# photodiodes.net
KiCad netlist of a schematic drawn in Altium Designer
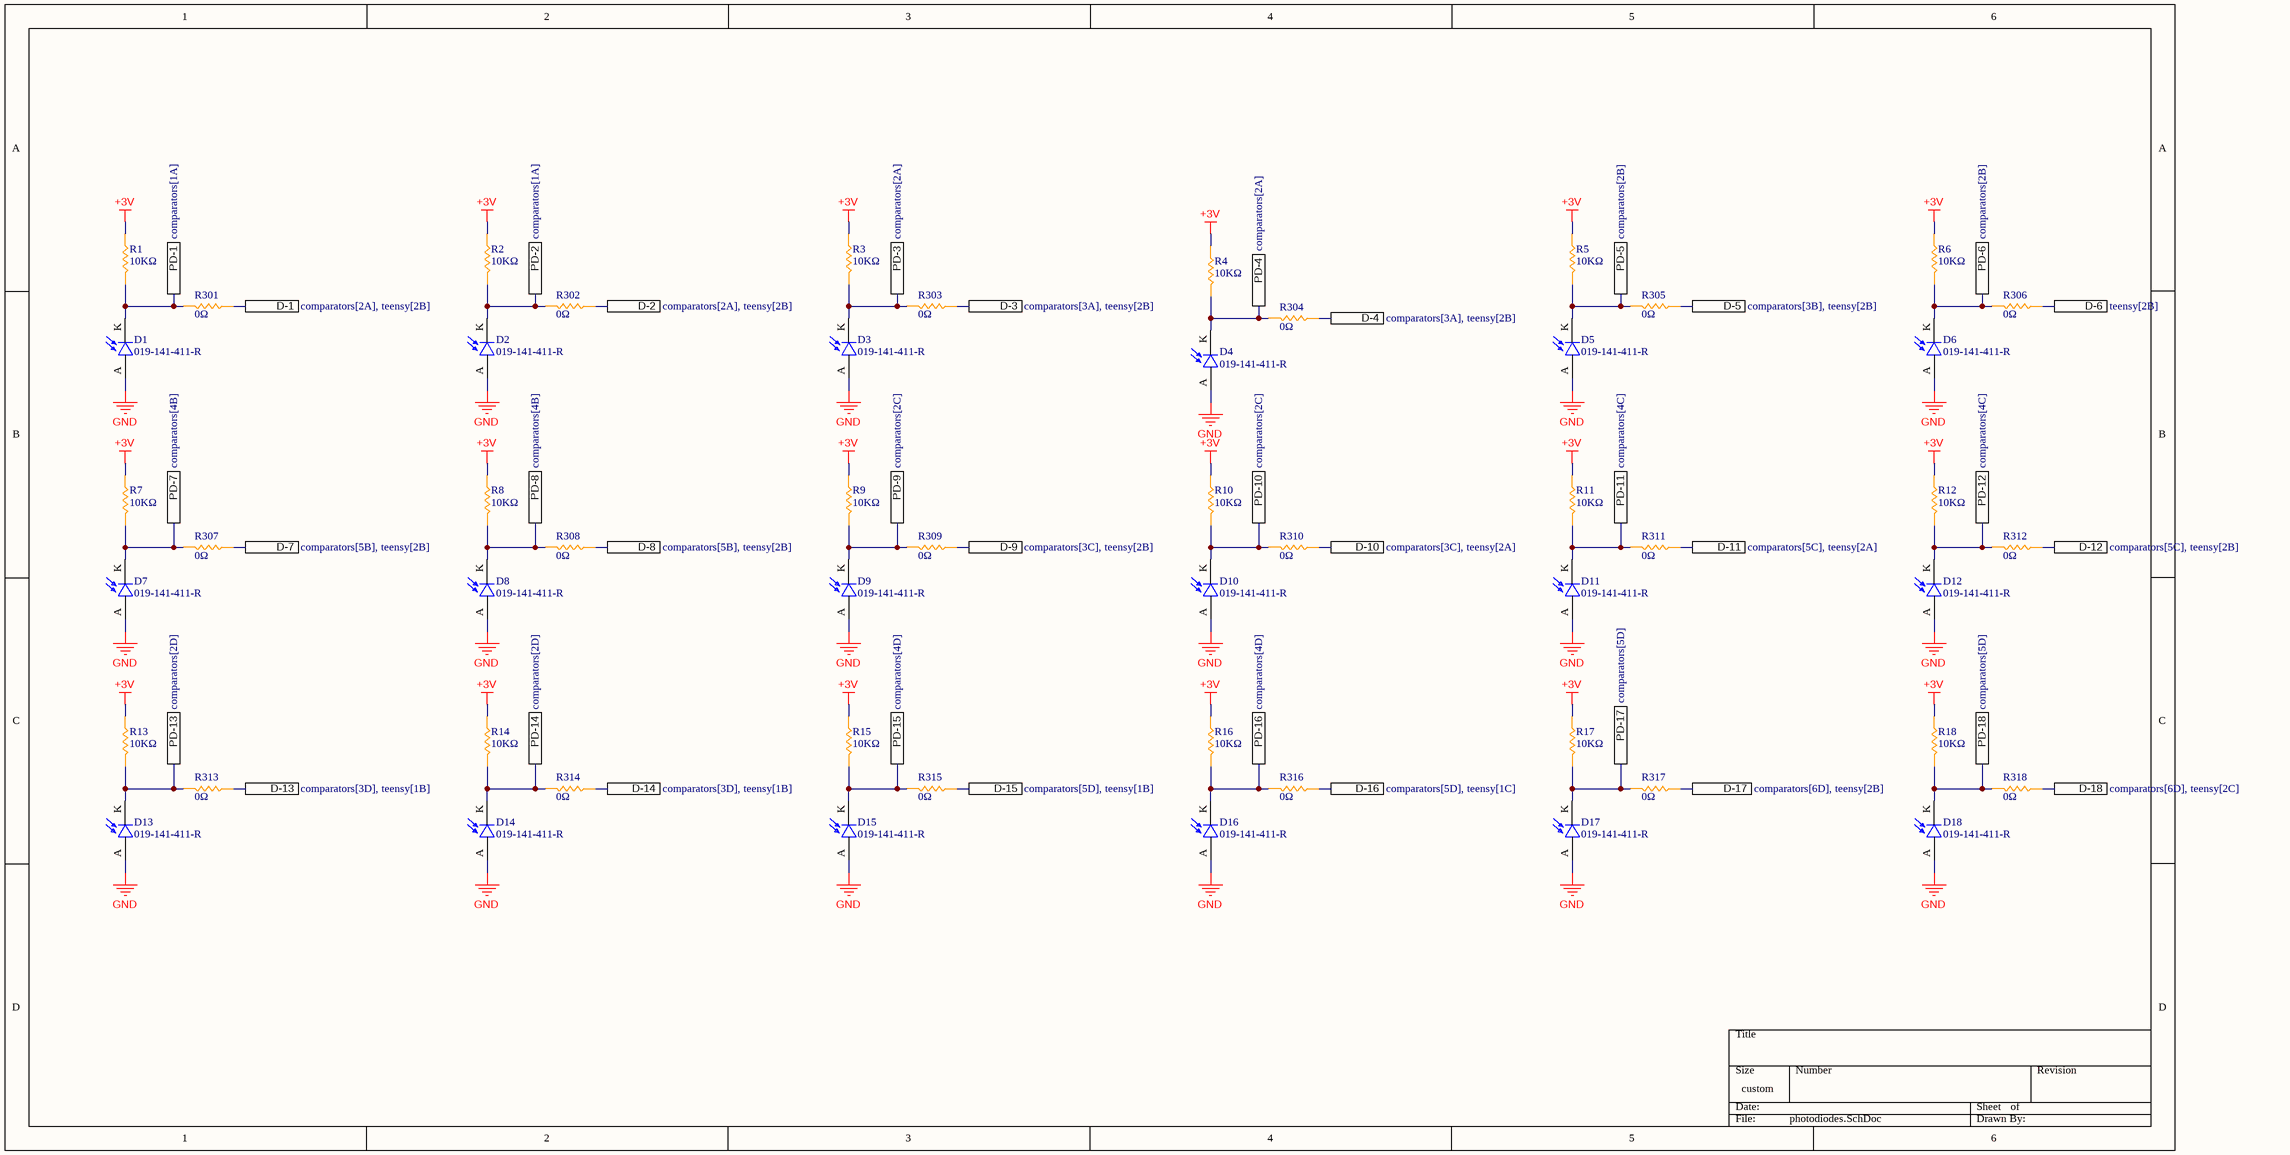
[diagram p0: photodiodes.SchDoc]

(export (version "E")
  (design (tool "Eeschema 10.0.6"))
  (components
    (comp (ref "D1")
      (value "019-141-411-R")
      (footprint "DIOC2012X80N")
      (description "PHOTODIODE RED MICRO SMT")
      (fields (field (name "MF") "Advanced Photonix"))
      (libsource (lib "019-141-411-R") (part "019-141-411-R"))
    )
    (comp (ref "D2")
      (value "019-141-411-R")
      (footprint "DIOC2012X80N")
      (description "PHOTODIODE RED MICRO SMT")
      (fields (field (name "MF") "Advanced Photonix"))
      (libsource (lib "019-141-411-R") (part "019-141-411-R"))
    )
    (comp (ref "D3")
      (value "019-141-411-R")
      (footprint "DIOC2012X80N")
      (description "PHOTODIODE RED MICRO SMT")
      (fields (field (name "MF") "Advanced Photonix"))
      (libsource (lib "019-141-411-R") (part "019-141-411-R"))
    )
    (comp (ref "D4")
      (value "019-141-411-R")
      (footprint "DIOC2012X80N")
      (description "PHOTODIODE RED MICRO SMT")
      (fields (field (name "MF") "Advanced Photonix"))
      (libsource (lib "019-141-411-R") (part "019-141-411-R"))
    )
    (comp (ref "D5")
      (value "019-141-411-R")
      (footprint "DIOC2012X80N")
      (description "PHOTODIODE RED MICRO SMT")
      (fields (field (name "MF") "Advanced Photonix"))
      (libsource (lib "019-141-411-R") (part "019-141-411-R"))
    )
    (comp (ref "D6")
      (value "019-141-411-R")
      (footprint "DIOC2012X80N")
      (description "PHOTODIODE RED MICRO SMT")
      (fields (field (name "MF") "Advanced Photonix"))
      (libsource (lib "019-141-411-R") (part "019-141-411-R"))
    )
    (comp (ref "D7")
      (value "019-141-411-R")
      (footprint "DIOC2012X80N")
      (description "PHOTODIODE RED MICRO SMT")
      (fields (field (name "MF") "Advanced Photonix"))
      (libsource (lib "019-141-411-R") (part "019-141-411-R"))
    )
    (comp (ref "D8")
      (value "019-141-411-R")
      (footprint "DIOC2012X80N")
      (description "PHOTODIODE RED MICRO SMT")
      (fields (field (name "MF") "Advanced Photonix"))
      (libsource (lib "019-141-411-R") (part "019-141-411-R"))
    )
    (comp (ref "D9")
      (value "019-141-411-R")
      (footprint "DIOC2012X80N")
      (description "PHOTODIODE RED MICRO SMT")
      (fields (field (name "MF") "Advanced Photonix"))
      (libsource (lib "019-141-411-R") (part "019-141-411-R"))
    )
    (comp (ref "D10")
      (value "019-141-411-R")
      (footprint "DIOC2012X80N")
      (description "PHOTODIODE RED MICRO SMT")
      (fields (field (name "MF") "Advanced Photonix"))
      (libsource (lib "019-141-411-R") (part "019-141-411-R"))
    )
    (comp (ref "D11")
      (value "019-141-411-R")
      (footprint "DIOC2012X80N")
      (description "PHOTODIODE RED MICRO SMT")
      (fields (field (name "MF") "Advanced Photonix"))
      (libsource (lib "019-141-411-R") (part "019-141-411-R"))
    )
    (comp (ref "D12")
      (value "019-141-411-R")
      (footprint "DIOC2012X80N")
      (description "PHOTODIODE RED MICRO SMT")
      (fields (field (name "MF") "Advanced Photonix"))
      (libsource (lib "019-141-411-R") (part "019-141-411-R"))
    )
    (comp (ref "D13")
      (value "019-141-411-R")
      (footprint "DIOC2012X80N")
      (description "PHOTODIODE RED MICRO SMT")
      (fields (field (name "MF") "Advanced Photonix"))
      (libsource (lib "019-141-411-R") (part "019-141-411-R"))
    )
    (comp (ref "D14")
      (value "019-141-411-R")
      (footprint "DIOC2012X80N")
      (description "PHOTODIODE RED MICRO SMT")
      (fields (field (name "MF") "Advanced Photonix"))
      (libsource (lib "019-141-411-R") (part "019-141-411-R"))
    )
    (comp (ref "D15")
      (value "019-141-411-R")
      (footprint "DIOC2012X80N")
      (description "PHOTODIODE RED MICRO SMT")
      (fields (field (name "MF") "Advanced Photonix"))
      (libsource (lib "019-141-411-R") (part "019-141-411-R"))
    )
    (comp (ref "D16")
      (value "019-141-411-R")
      (footprint "DIOC2012X80N")
      (description "PHOTODIODE RED MICRO SMT")
      (fields (field (name "MF") "Advanced Photonix"))
      (libsource (lib "019-141-411-R") (part "019-141-411-R"))
    )
    (comp (ref "D17")
      (value "019-141-411-R")
      (footprint "DIOC2012X80N")
      (description "PHOTODIODE RED MICRO SMT")
      (fields (field (name "MF") "Advanced Photonix"))
      (libsource (lib "019-141-411-R") (part "019-141-411-R"))
    )
    (comp (ref "D18")
      (value "019-141-411-R")
      (footprint "DIOC2012X80N")
      (description "PHOTODIODE RED MICRO SMT")
      (fields (field (name "MF") "Advanced Photonix"))
      (libsource (lib "019-141-411-R") (part "019-141-411-R"))
    )
    (comp (ref "R1")
      (value "10KΩ")
      (footprint "RES_0603")
      (description "Resistor SMD 0603 generic")
      (libsource (lib "RC") (part "RES_0603"))
    )
    (comp (ref "R2")
      (value "10KΩ")
      (footprint "RES_0603")
      (description "Resistor SMD 0603 generic")
      (libsource (lib "RC") (part "RES_0603"))
    )
    (comp (ref "R3")
      (value "10KΩ")
      (footprint "RES_0603")
      (description "Resistor SMD 0603 generic")
      (libsource (lib "RC") (part "RES_0603"))
    )
    (comp (ref "R4")
      (value "10KΩ")
      (footprint "RES_0603")
      (description "Resistor SMD 0603 generic")
      (libsource (lib "RC") (part "RES_0603"))
    )
    (comp (ref "R5")
      (value "10KΩ")
      (footprint "RES_0603")
      (description "Resistor SMD 0603 generic")
      (libsource (lib "RC") (part "RES_0603"))
    )
    (comp (ref "R6")
      (value "10KΩ")
      (footprint "RES_0603")
      (description "Resistor SMD 0603 generic")
      (libsource (lib "RC") (part "RES_0603"))
    )
    (comp (ref "R7")
      (value "10KΩ")
      (footprint "RES_0603")
      (description "Resistor SMD 0603 generic")
      (libsource (lib "RC") (part "RES_0603"))
    )
    (comp (ref "R8")
      (value "10KΩ")
      (footprint "RES_0603")
      (description "Resistor SMD 0603 generic")
      (libsource (lib "RC") (part "RES_0603"))
    )
    (comp (ref "R9")
      (value "10KΩ")
      (footprint "RES_0603")
      (description "Resistor SMD 0603 generic")
      (libsource (lib "RC") (part "RES_0603"))
    )
    (comp (ref "R10")
      (value "10KΩ")
      (footprint "RES_0603")
      (description "Resistor SMD 0603 generic")
      (libsource (lib "RC") (part "RES_0603"))
    )
    (comp (ref "R11")
      (value "10KΩ")
      (footprint "RES_0603")
      (description "Resistor SMD 0603 generic")
      (libsource (lib "RC") (part "RES_0603"))
    )
    (comp (ref "R12")
      (value "10KΩ")
      (footprint "RES_0603")
      (description "Resistor SMD 0603 generic")
      (libsource (lib "RC") (part "RES_0603"))
    )
    (comp (ref "R13")
      (value "10KΩ")
      (footprint "RES_0603")
      (description "Resistor SMD 0603 generic")
      (libsource (lib "RC") (part "RES_0603"))
    )
    (comp (ref "R14")
      (value "10KΩ")
      (footprint "RES_0603")
      (description "Resistor SMD 0603 generic")
      (libsource (lib "RC") (part "RES_0603"))
    )
    (comp (ref "R15")
      (value "10KΩ")
      (footprint "RES_0603")
      (description "Resistor SMD 0603 generic")
      (libsource (lib "RC") (part "RES_0603"))
    )
    (comp (ref "R16")
      (value "10KΩ")
      (footprint "RES_0603")
      (description "Resistor SMD 0603 generic")
      (libsource (lib "RC") (part "RES_0603"))
    )
    (comp (ref "R17")
      (value "10KΩ")
      (footprint "RES_0603")
      (description "Resistor SMD 0603 generic")
      (libsource (lib "RC") (part "RES_0603"))
    )
    (comp (ref "R18")
      (value "10KΩ")
      (footprint "RES_0603")
      (description "Resistor SMD 0603 generic")
      (libsource (lib "RC") (part "RES_0603"))
    )
    (comp (ref "R301")
      (value "0Ω")
      (footprint "RES_0603")
      (description "Resistor SMD 0603 generic")
      (libsource (lib "RC") (part "RES_0603"))
    )
    (comp (ref "R302")
      (value "0Ω")
      (footprint "RES_0603")
      (description "Resistor SMD 0603 generic")
      (libsource (lib "RC") (part "RES_0603"))
    )
    (comp (ref "R303")
      (value "0Ω")
      (footprint "RES_0603")
      (description "Resistor SMD 0603 generic")
      (libsource (lib "RC") (part "RES_0603"))
    )
    (comp (ref "R304")
      (value "0Ω")
      (footprint "RES_0603")
      (description "Resistor SMD 0603 generic")
      (libsource (lib "RC") (part "RES_0603"))
    )
    (comp (ref "R305")
      (value "0Ω")
      (footprint "RES_0603")
      (description "Resistor SMD 0603 generic")
      (libsource (lib "RC") (part "RES_0603"))
    )
    (comp (ref "R306")
      (value "0Ω")
      (footprint "RES_0603")
      (description "Resistor SMD 0603 generic")
      (libsource (lib "RC") (part "RES_0603"))
    )
    (comp (ref "R307")
      (value "0Ω")
      (footprint "RES_0603")
      (description "Resistor SMD 0603 generic")
      (libsource (lib "RC") (part "RES_0603"))
    )
    (comp (ref "R308")
      (value "0Ω")
      (footprint "RES_0603")
      (description "Resistor SMD 0603 generic")
      (libsource (lib "RC") (part "RES_0603"))
    )
    (comp (ref "R309")
      (value "0Ω")
      (footprint "RES_0603")
      (description "Resistor SMD 0603 generic")
      (libsource (lib "RC") (part "RES_0603"))
    )
    (comp (ref "R310")
      (value "0Ω")
      (footprint "RES_0603")
      (description "Resistor SMD 0603 generic")
      (libsource (lib "RC") (part "RES_0603"))
    )
    (comp (ref "R311")
      (value "0Ω")
      (footprint "RES_0603")
      (description "Resistor SMD 0603 generic")
      (libsource (lib "RC") (part "RES_0603"))
    )
    (comp (ref "R312")
      (value "0Ω")
      (footprint "RES_0603")
      (description "Resistor SMD 0603 generic")
      (libsource (lib "RC") (part "RES_0603"))
    )
    (comp (ref "R313")
      (value "0Ω")
      (footprint "RES_0603")
      (description "Resistor SMD 0603 generic")
      (libsource (lib "RC") (part "RES_0603"))
    )
    (comp (ref "R314")
      (value "0Ω")
      (footprint "RES_0603")
      (description "Resistor SMD 0603 generic")
      (libsource (lib "RC") (part "RES_0603"))
    )
    (comp (ref "R315")
      (value "0Ω")
      (footprint "RES_0603")
      (description "Resistor SMD 0603 generic")
      (libsource (lib "RC") (part "RES_0603"))
    )
    (comp (ref "R316")
      (value "0Ω")
      (footprint "RES_0603")
      (description "Resistor SMD 0603 generic")
      (libsource (lib "RC") (part "RES_0603"))
    )
    (comp (ref "R317")
      (value "0Ω")
      (footprint "RES_0603")
      (description "Resistor SMD 0603 generic")
      (libsource (lib "RC") (part "RES_0603"))
    )
    (comp (ref "R318")
      (value "0Ω")
      (footprint "RES_0603")
      (description "Resistor SMD 0603 generic")
      (libsource (lib "RC") (part "RES_0603"))
    )
  )
  (nets
    (net (code "1") (name "+3V") (class "Default")
      (node (ref "R1") (pin "2") (pintype "passive"))
      (node (ref "R10") (pin "2") (pintype "passive"))
      (node (ref "R11") (pin "2") (pintype "passive"))
      (node (ref "R12") (pin "2") (pintype "passive"))
      (node (ref "R13") (pin "2") (pintype "passive"))
      (node (ref "R14") (pin "2") (pintype "passive"))
      (node (ref "R15") (pin "2") (pintype "passive"))
      (node (ref "R16") (pin "2") (pintype "passive"))
      (node (ref "R17") (pin "2") (pintype "passive"))
      (node (ref "R18") (pin "2") (pintype "passive"))
      (node (ref "R2") (pin "2") (pintype "passive"))
      (node (ref "R3") (pin "2") (pintype "passive"))
      (node (ref "R4") (pin "2") (pintype "passive"))
      (node (ref "R5") (pin "2") (pintype "passive"))
      (node (ref "R6") (pin "2") (pintype "passive"))
      (node (ref "R7") (pin "2") (pintype "passive"))
      (node (ref "R8") (pin "2") (pintype "passive"))
      (node (ref "R9") (pin "2") (pintype "passive"))
    )
    (net (code "2") (name "/D-1") (class "Default") (node (ref "R301") (pin "2") (pintype "passive")))
    (net (code "3") (name "/D-2") (class "Default") (node (ref "R302") (pin "2") (pintype "passive")))
    (net (code "4") (name "/D-3") (class "Default") (node (ref "R303") (pin "2") (pintype "passive")))
    (net (code "5") (name "/D-4") (class "Default") (node (ref "R304") (pin "2") (pintype "passive")))
    (net (code "6") (name "/D-5") (class "Default") (node (ref "R305") (pin "2") (pintype "passive")))
    (net (code "7") (name "/D-6") (class "Default") (node (ref "R306") (pin "2") (pintype "passive")))
    (net (code "8") (name "/D-7") (class "Default") (node (ref "R307") (pin "2") (pintype "passive")))
    (net (code "9") (name "/D-8") (class "Default") (node (ref "R308") (pin "2") (pintype "passive")))
    (net (code "10") (name "/D-9") (class "Default") (node (ref "R309") (pin "2") (pintype "passive")))
    (net (code "11") (name "/D-10") (class "Default") (node (ref "R310") (pin "2") (pintype "passive")))
    (net (code "12") (name "/D-11") (class "Default") (node (ref "R311") (pin "2") (pintype "passive")))
    (net (code "13") (name "/D-12") (class "Default") (node (ref "R312") (pin "2") (pintype "passive")))
    (net (code "14") (name "/D-13") (class "Default") (node (ref "R313") (pin "2") (pintype "passive")))
    (net (code "15") (name "/D-14") (class "Default") (node (ref "R314") (pin "2") (pintype "passive")))
    (net (code "16") (name "/D-15") (class "Default") (node (ref "R315") (pin "2") (pintype "passive")))
    (net (code "17") (name "/D-16") (class "Default") (node (ref "R316") (pin "2") (pintype "passive")))
    (net (code "18") (name "/D-17") (class "Default") (node (ref "R317") (pin "2") (pintype "passive")))
    (net (code "19") (name "/D-18") (class "Default") (node (ref "R318") (pin "2") (pintype "passive")))
    (net (code "20") (name "/PD-1") (class "Default")
      (node (ref "D1") (pin "K") (pinfunction "C_K") (pintype "passive"))
      (node (ref "R1") (pin "1") (pintype "passive"))
      (node (ref "R301") (pin "1") (pintype "passive"))
    )
    (net (code "21") (name "/PD-2") (class "Default")
      (node (ref "D2") (pin "K") (pinfunction "C_K") (pintype "passive"))
      (node (ref "R2") (pin "1") (pintype "passive"))
      (node (ref "R302") (pin "1") (pintype "passive"))
    )
    (net (code "22") (name "/PD-3") (class "Default")
      (node (ref "D3") (pin "K") (pinfunction "C_K") (pintype "passive"))
      (node (ref "R3") (pin "1") (pintype "passive"))
      (node (ref "R303") (pin "1") (pintype "passive"))
    )
    (net (code "23") (name "/PD-4") (class "Default")
      (node (ref "D4") (pin "K") (pinfunction "C_K") (pintype "passive"))
      (node (ref "R304") (pin "1") (pintype "passive"))
      (node (ref "R4") (pin "1") (pintype "passive"))
    )
    (net (code "24") (name "/PD-5") (class "Default")
      (node (ref "D5") (pin "K") (pinfunction "C_K") (pintype "passive"))
      (node (ref "R305") (pin "1") (pintype "passive"))
      (node (ref "R5") (pin "1") (pintype "passive"))
    )
    (net (code "25") (name "/PD-6") (class "Default")
      (node (ref "D6") (pin "K") (pinfunction "C_K") (pintype "passive"))
      (node (ref "R306") (pin "1") (pintype "passive"))
      (node (ref "R6") (pin "1") (pintype "passive"))
    )
    (net (code "26") (name "/PD-7") (class "Default")
      (node (ref "D7") (pin "K") (pinfunction "C_K") (pintype "passive"))
      (node (ref "R307") (pin "1") (pintype "passive"))
      (node (ref "R7") (pin "1") (pintype "passive"))
    )
    (net (code "27") (name "/PD-8") (class "Default")
      (node (ref "D8") (pin "K") (pinfunction "C_K") (pintype "passive"))
      (node (ref "R308") (pin "1") (pintype "passive"))
      (node (ref "R8") (pin "1") (pintype "passive"))
    )
    (net (code "28") (name "/PD-9") (class "Default")
      (node (ref "D9") (pin "K") (pinfunction "C_K") (pintype "passive"))
      (node (ref "R309") (pin "1") (pintype "passive"))
      (node (ref "R9") (pin "1") (pintype "passive"))
    )
    (net (code "29") (name "/PD-10") (class "Default")
      (node (ref "D10") (pin "K") (pinfunction "C_K") (pintype "passive"))
      (node (ref "R10") (pin "1") (pintype "passive"))
      (node (ref "R310") (pin "1") (pintype "passive"))
    )
    (net (code "30") (name "/PD-11") (class "Default")
      (node (ref "D11") (pin "K") (pinfunction "C_K") (pintype "passive"))
      (node (ref "R11") (pin "1") (pintype "passive"))
      (node (ref "R311") (pin "1") (pintype "passive"))
    )
    (net (code "31") (name "/PD-12") (class "Default")
      (node (ref "D12") (pin "K") (pinfunction "C_K") (pintype "passive"))
      (node (ref "R12") (pin "1") (pintype "passive"))
      (node (ref "R312") (pin "1") (pintype "passive"))
    )
    (net (code "32") (name "/PD-13") (class "Default")
      (node (ref "D13") (pin "K") (pinfunction "C_K") (pintype "passive"))
      (node (ref "R13") (pin "1") (pintype "passive"))
      (node (ref "R313") (pin "1") (pintype "passive"))
    )
    (net (code "33") (name "/PD-14") (class "Default")
      (node (ref "D14") (pin "K") (pinfunction "C_K") (pintype "passive"))
      (node (ref "R14") (pin "1") (pintype "passive"))
      (node (ref "R314") (pin "1") (pintype "passive"))
    )
    (net (code "34") (name "/PD-15") (class "Default")
      (node (ref "D15") (pin "K") (pinfunction "C_K") (pintype "passive"))
      (node (ref "R15") (pin "1") (pintype "passive"))
      (node (ref "R315") (pin "1") (pintype "passive"))
    )
    (net (code "35") (name "/PD-16") (class "Default")
      (node (ref "D16") (pin "K") (pinfunction "C_K") (pintype "passive"))
      (node (ref "R16") (pin "1") (pintype "passive"))
      (node (ref "R316") (pin "1") (pintype "passive"))
    )
    (net (code "36") (name "/PD-17") (class "Default")
      (node (ref "D17") (pin "K") (pinfunction "C_K") (pintype "passive"))
      (node (ref "R17") (pin "1") (pintype "passive"))
      (node (ref "R317") (pin "1") (pintype "passive"))
    )
    (net (code "37") (name "/PD-18") (class "Default")
      (node (ref "D18") (pin "K") (pinfunction "C_K") (pintype "passive"))
      (node (ref "R18") (pin "1") (pintype "passive"))
      (node (ref "R318") (pin "1") (pintype "passive"))
    )
    (net (code "38") (name "GND") (class "Default")
      (node (ref "D1") (pin "A") (pinfunction "A_A") (pintype "passive"))
      (node (ref "D10") (pin "A") (pinfunction "A_A") (pintype "passive"))
      (node (ref "D11") (pin "A") (pinfunction "A_A") (pintype "passive"))
      (node (ref "D12") (pin "A") (pinfunction "A_A") (pintype "passive"))
      (node (ref "D13") (pin "A") (pinfunction "A_A") (pintype "passive"))
      (node (ref "D14") (pin "A") (pinfunction "A_A") (pintype "passive"))
      (node (ref "D15") (pin "A") (pinfunction "A_A") (pintype "passive"))
      (node (ref "D16") (pin "A") (pinfunction "A_A") (pintype "passive"))
      (node (ref "D17") (pin "A") (pinfunction "A_A") (pintype "passive"))
      (node (ref "D18") (pin "A") (pinfunction "A_A") (pintype "passive"))
      (node (ref "D2") (pin "A") (pinfunction "A_A") (pintype "passive"))
      (node (ref "D3") (pin "A") (pinfunction "A_A") (pintype "passive"))
      (node (ref "D4") (pin "A") (pinfunction "A_A") (pintype "passive"))
      (node (ref "D5") (pin "A") (pinfunction "A_A") (pintype "passive"))
      (node (ref "D6") (pin "A") (pinfunction "A_A") (pintype "passive"))
      (node (ref "D7") (pin "A") (pinfunction "A_A") (pintype "passive"))
      (node (ref "D8") (pin "A") (pinfunction "A_A") (pintype "passive"))
      (node (ref "D9") (pin "A") (pinfunction "A_A") (pintype "passive"))
    )
  )
)
